# OPAMP_TESTER.net
KiCad netlist of a schematic drawn in Altium Designer
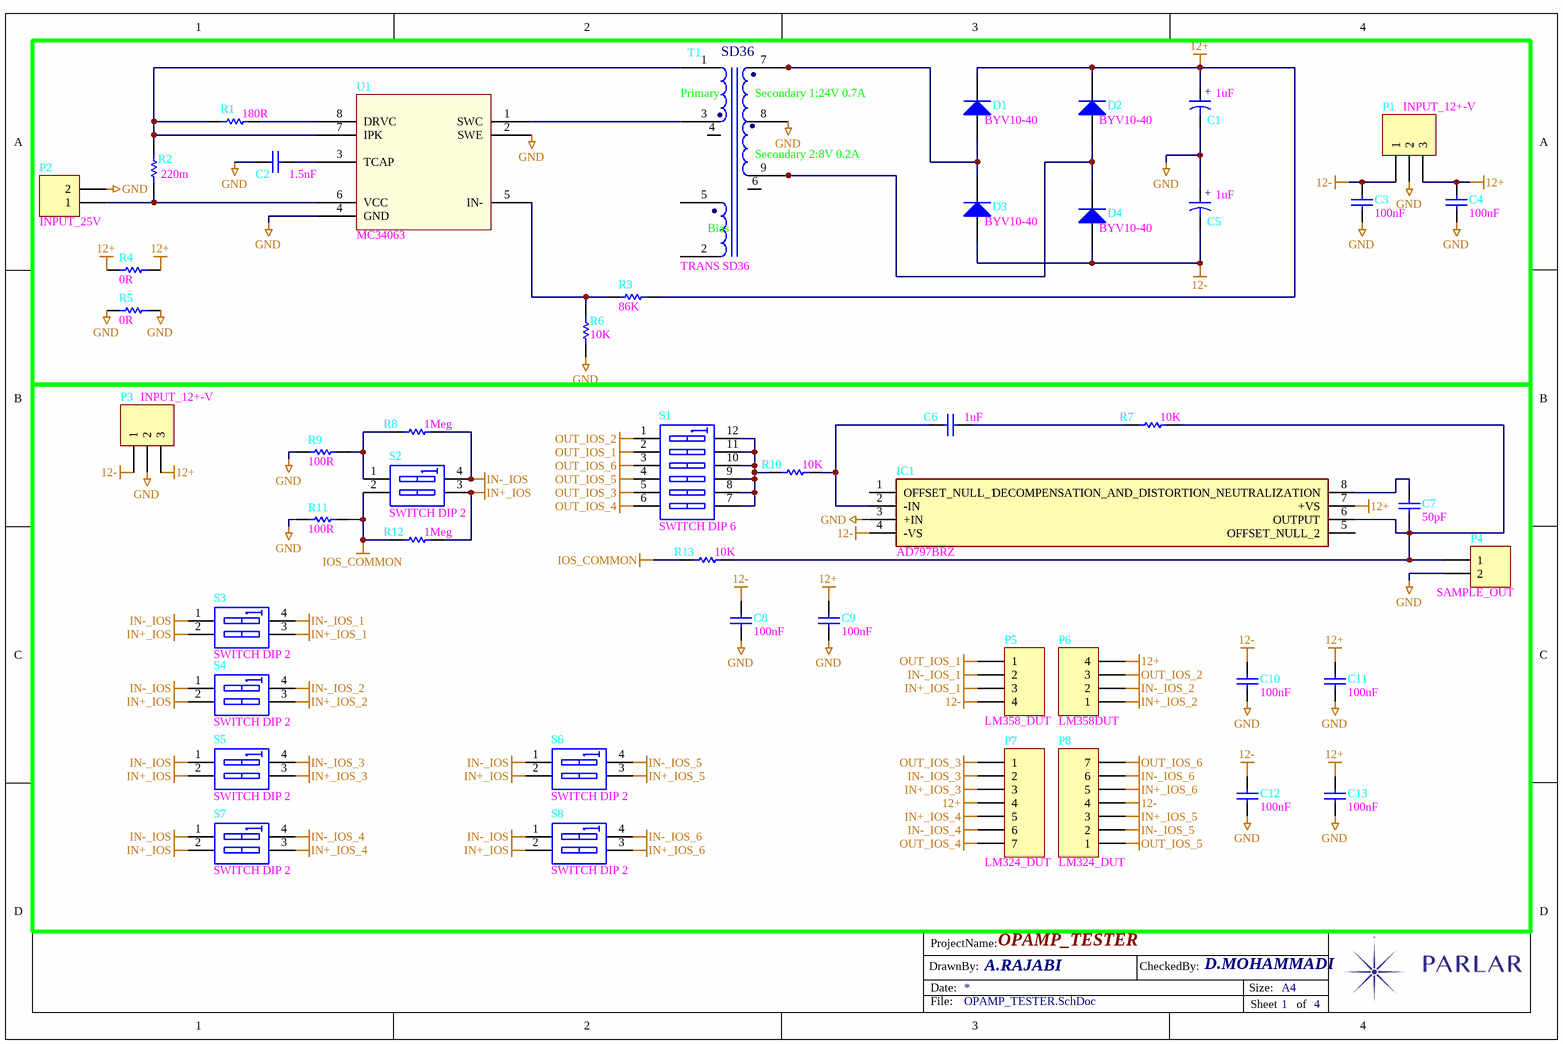
[diagram p0: OPAMP_TESTER.SchDoc]

(export (version "E")
  (design (tool "Eeschema 10.0.6"))
  (components
    (comp (ref "C1")
      (value "1uF")
      (footprint "CAP EL D06.3 P2.5")
      (description "Capacitor  Polarized")
      (fields (field (name "PUBLISHER") "Altium Limited"))
      (libsource (lib "Parlarlib_30") (part "CAP POL"))
    )
    (comp (ref "C2")
      (value "1.5nF")
      (footprint "SMD 0805")
      (description "Capacitor")
      (fields (field (name "PUBLISHER") "Altium Limited"))
      (libsource (lib "Parlarlib_30") (part "CAP"))
    )
    (comp (ref "C3")
      (value "100nF")
      (footprint "SMD 0805")
      (description "Capacitor")
      (fields (field (name "PUBLISHER") "Altium Limited"))
      (libsource (lib "Parlarlib_30") (part "CAP"))
    )
    (comp (ref "C4")
      (value "100nF")
      (footprint "SMD 0805")
      (description "Capacitor")
      (fields (field (name "PUBLISHER") "Altium Limited"))
      (libsource (lib "Parlarlib_30") (part "CAP"))
    )
    (comp (ref "C5")
      (value "1uF")
      (footprint "CAP EL D06.3 P2.5")
      (description "Capacitor  Polarized")
      (fields (field (name "PUBLISHER") "Altium Limited"))
      (libsource (lib "Parlarlib_30") (part "CAP POL"))
    )
    (comp (ref "C6")
      (value "1uF")
      (footprint "SMD 1206")
      (description "Capacitor")
      (fields (field (name "PUBLISHER") "Altium Limited"))
      (libsource (lib "Parlarlib_30") (part "CAP"))
    )
    (comp (ref "C7")
      (value "50pF")
      (footprint "SMD 1206")
      (description "Capacitor")
      (fields (field (name "PUBLISHER") "Altium Limited"))
      (libsource (lib "Parlarlib_30") (part "CAP"))
    )
    (comp (ref "C8")
      (value "100nF")
      (footprint "SMD 0805")
      (description "Capacitor")
      (fields (field (name "PUBLISHER") "Altium Limited"))
      (libsource (lib "Parlarlib_30") (part "CAP"))
    )
    (comp (ref "C9")
      (value "100nF")
      (footprint "SMD 0805")
      (description "Capacitor")
      (fields (field (name "PUBLISHER") "Altium Limited"))
      (libsource (lib "Parlarlib_30") (part "CAP"))
    )
    (comp (ref "C10")
      (value "100nF")
      (footprint "SMD 0805")
      (description "Capacitor")
      (fields (field (name "PUBLISHER") "Altium Limited"))
      (libsource (lib "Parlarlib_30") (part "CAP"))
    )
    (comp (ref "C11")
      (value "100nF")
      (footprint "SMD 0805")
      (description "Capacitor")
      (fields (field (name "PUBLISHER") "Altium Limited"))
      (libsource (lib "Parlarlib_30") (part "CAP"))
    )
    (comp (ref "C12")
      (value "100nF")
      (footprint "SMD 0805")
      (description "Capacitor")
      (fields (field (name "PUBLISHER") "Altium Limited"))
      (libsource (lib "Parlarlib_30") (part "CAP"))
    )
    (comp (ref "C13")
      (value "100nF")
      (footprint "SMD 0805")
      (description "Capacitor")
      (fields (field (name "PUBLISHER") "Altium Limited"))
      (libsource (lib "Parlarlib_30") (part "CAP"))
    )
    (comp (ref "D1")
      (value "BYV10-40")
      (footprint "SMD SMA")
      (description "Typical Diode")
      (libsource (lib "Parlarlib_30") (part "DIODE"))
    )
    (comp (ref "D2")
      (value "BYV10-40")
      (footprint "SMD SMA")
      (description "Typical Diode")
      (libsource (lib "Parlarlib_30") (part "DIODE"))
    )
    (comp (ref "D3")
      (value "BYV10-40")
      (footprint "SMD SMA")
      (description "Typical Diode")
      (libsource (lib "Parlarlib_30") (part "DIODE"))
    )
    (comp (ref "D4")
      (value "BYV10-40")
      (footprint "SMD SMA")
      (description "Typical Diode")
      (libsource (lib "Parlarlib_30") (part "DIODE"))
    )
    (comp (ref "IC1")
      (value "AD797BRZ")
      (footprint "SamacSys:SOIC127P600X175-8N")
      (description "Integrated Circuit")
      (fields (field (name "MOUSER PART NUMBER") "584-AD797BRZ"))
      (libsource (lib "*") (part "AD797BRZ"))
    )
    (comp (ref "P1")
      (value "INPUT_12+-V")
      (footprint "CON XH 3")
      (description "Header, 3-Pin")
      (fields (field (name "PUBLISHER") "Altium Limited"))
      (libsource (lib "Parlarlib_30") (part "CONNECTOR 3"))
    )
    (comp (ref "P2")
      (value "INPUT_25V")
      (footprint "CON XH RA 2")
      (description "Header, 2-Pin")
      (fields (field (name "PUBLISHER") "Altium Limited"))
      (libsource (lib "Parlarlib_30") (part "CONNECTOR 2"))
    )
    (comp (ref "P3")
      (value "INPUT_12+-V")
      (footprint "CON XH 3")
      (description "Header, 3-Pin")
      (fields (field (name "PUBLISHER") "Altium Limited"))
      (libsource (lib "Parlarlib_30") (part "CONNECTOR 3"))
    )
    (comp (ref "P4")
      (value "SAMPLE_OUT")
      (footprint "CON XH 2")
      (description "Header, 2-Pin")
      (fields (field (name "PUBLISHER") "Altium Limited"))
      (libsource (lib "") (part "CONNECTOR 2_1"))
    )
    (comp (ref "P5")
      (value "LM358_DUT")
      (footprint "CON HDR 2.54FM 4")
      (description "Header, 4-Pin")
      (fields (field (name "PUBLISHER") "Altium Limited"))
      (libsource (lib "Parlarlib_30") (part "CONNECTOR 4"))
    )
    (comp (ref "P6")
      (value "LM358DUT")
      (footprint "CON HDR 2.54FM 4")
      (description "Header, 4-Pin")
      (fields (field (name "PUBLISHER") "Altium Limited"))
      (libsource (lib "") (part "CONNECTOR 4_1"))
    )
    (comp (ref "P7")
      (value "LM324_DUT")
      (footprint "CON HDR 2.54FM 7")
      (description "Header, 7-Pin")
      (fields (field (name "PUBLISHER") "Altium Limited"))
      (libsource (lib "") (part "CONNECTOR 7_1"))
    )
    (comp (ref "P8")
      (value "LM324_DUT")
      (footprint "CON HDR 2.54FM 7")
      (description "Header, 7-Pin")
      (fields (field (name "PUBLISHER") "Altium Limited"))
      (libsource (lib "Parlarlib_30") (part "CONNECTOR 7"))
    )
    (comp (ref "R1")
      (value "180R")
      (footprint "SMD 0805")
      (description "Resistor")
      (libsource (lib "Parlarlib_30") (part "RES"))
    )
    (comp (ref "R2")
      (value "220m")
      (footprint "SMD 0805")
      (description "Resistor")
      (libsource (lib "Parlarlib_30") (part "RES"))
    )
    (comp (ref "R3")
      (value "86K")
      (footprint "SMD 1206")
      (description "Resistor")
      (libsource (lib "Parlarlib_30") (part "RES"))
    )
    (comp (ref "R4")
      (value "0R")
      (footprint "SMD 1206")
      (description "Resistor")
      (libsource (lib "Parlarlib_30") (part "RES"))
    )
    (comp (ref "R5")
      (value "0R")
      (footprint "SMD 1206")
      (description "Resistor")
      (libsource (lib "Parlarlib_30") (part "RES"))
    )
    (comp (ref "R6")
      (value "10K")
      (footprint "SMD 0805")
      (description "Resistor")
      (libsource (lib "Parlarlib_30") (part "RES"))
    )
    (comp (ref "R7")
      (value "10K")
      (footprint "SMD 0805")
      (description "Resistor")
      (libsource (lib "Parlarlib_30") (part "RES"))
    )
    (comp (ref "R8")
      (value "1Meg")
      (footprint "SMD 0805")
      (description "Resistor")
      (libsource (lib "Parlarlib_30") (part "RES"))
    )
    (comp (ref "R9")
      (value "100R")
      (footprint "SMD 0805")
      (description "Resistor")
      (libsource (lib "Parlarlib_30") (part "RES"))
    )
    (comp (ref "R10")
      (value "10K")
      (footprint "SMD 1206")
      (description "Resistor")
      (libsource (lib "Parlarlib_30") (part "RES"))
    )
    (comp (ref "R11")
      (value "100R")
      (footprint "SMD 0805")
      (description "Resistor")
      (libsource (lib "Parlarlib_30") (part "RES"))
    )
    (comp (ref "R12")
      (value "1Meg")
      (footprint "SMD 0805")
      (description "Resistor")
      (libsource (lib "Parlarlib_30") (part "RES"))
    )
    (comp (ref "R13")
      (value "10K")
      (footprint "SMD 0805")
      (description "Resistor")
      (libsource (lib "Parlarlib_30") (part "RES"))
    )
    (comp (ref "S1")
      (value "SWITCH DIP 6")
      (footprint "SWITCH DIP 6")
      (description "DIP Switch, 6 Position, SPST")
      (fields (field (name "PUBLISHER") "Altium Limited"))
      (libsource (lib "Parlarlib_30") (part "SWITCH DIP 6"))
    )
    (comp (ref "S2")
      (value "SWITCH DIP 2")
      (footprint "SWITCH DIP 2")
      (description "DIP Switch, 2 Position, SPST")
      (fields (field (name "PUBLISHER") "Altium Limited"))
      (libsource (lib "Parlarlib_30") (part "SWITCH DIP 2"))
    )
    (comp (ref "S3")
      (value "SWITCH DIP 2")
      (footprint "SWITCH DIP 2")
      (description "DIP Switch, 2 Position, SPST")
      (fields (field (name "PUBLISHER") "Altium Limited"))
      (libsource (lib "Parlarlib_30") (part "SWITCH DIP 2"))
    )
    (comp (ref "S4")
      (value "SWITCH DIP 2")
      (footprint "SWITCH DIP 2")
      (description "DIP Switch, 2 Position, SPST")
      (fields (field (name "PUBLISHER") "Altium Limited"))
      (libsource (lib "Parlarlib_30") (part "SWITCH DIP 2"))
    )
    (comp (ref "S5")
      (value "SWITCH DIP 2")
      (footprint "SWITCH DIP 2")
      (description "DIP Switch, 2 Position, SPST")
      (fields (field (name "PUBLISHER") "Altium Limited"))
      (libsource (lib "Parlarlib_30") (part "SWITCH DIP 2"))
    )
    (comp (ref "S6")
      (value "SWITCH DIP 2")
      (footprint "SWITCH DIP 2")
      (description "DIP Switch, 2 Position, SPST")
      (fields (field (name "PUBLISHER") "Altium Limited"))
      (libsource (lib "Parlarlib_30") (part "SWITCH DIP 2"))
    )
    (comp (ref "S7")
      (value "SWITCH DIP 2")
      (footprint "SWITCH DIP 2")
      (description "DIP Switch, 2 Position, SPST")
      (fields (field (name "PUBLISHER") "Altium Limited"))
      (libsource (lib "Parlarlib_30") (part "SWITCH DIP 2"))
    )
    (comp (ref "S8")
      (value "SWITCH DIP 2")
      (footprint "SWITCH DIP 2")
      (description "DIP Switch, 2 Position, SPST")
      (fields (field (name "PUBLISHER") "Altium Limited"))
      (libsource (lib "Parlarlib_30") (part "SWITCH DIP 2"))
    )
    (comp (ref "T1")
      (value "TRANS SD36")
      (footprint "TR EC28/20 VER 5+5")
      (description "Transformer")
      (libsource (lib "Parlarlib_30") (part "TRANS SD36"))
    )
    (comp (ref "U1")
      (value "MC34063")
      (footprint "SMD IC SOP8")
      (libsource (lib "Parlarlib_30") (part "IC MC34063"))
    )
  )
  (nets
    (net (code "1") (name "12+") (class "Default")
      (node (ref "C1") (pin "1") (pinfunction "1_1") (pintype "passive"))
      (node (ref "C11") (pin "2") (pinfunction "2_2") (pintype "passive"))
      (node (ref "C13") (pin "2") (pinfunction "2_2") (pintype "passive"))
      (node (ref "C4") (pin "2") (pinfunction "2_2") (pintype "passive"))
      (node (ref "C9") (pin "2") (pinfunction "2_2") (pintype "passive"))
      (node (ref "D1") (pin "2") (pinfunction "2_2") (pintype "passive"))
      (node (ref "D2") (pin "2") (pinfunction "2_2") (pintype "passive"))
      (node (ref "IC1") (pin "7") (pinfunction "+VS_7") (pintype "passive"))
      (node (ref "P1") (pin "3") (pinfunction "3_3") (pintype "passive"))
      (node (ref "P3") (pin "3") (pinfunction "3_3") (pintype "passive"))
      (node (ref "P6") (pin "4") (pinfunction "4_4") (pintype "passive"))
      (node (ref "P7") (pin "4") (pinfunction "4_4") (pintype "passive"))
      (node (ref "R3") (pin "2") (pinfunction "2_2") (pintype "passive"))
      (node (ref "R4") (pin "1") (pinfunction "1_1") (pintype "passive"))
      (node (ref "R4") (pin "2") (pinfunction "2_2") (pintype "passive"))
    )
    (net (code "2") (name "12-") (class "Default")
      (node (ref "C10") (pin "2") (pinfunction "2_2") (pintype "passive"))
      (node (ref "C12") (pin "2") (pinfunction "2_2") (pintype "passive"))
      (node (ref "C3") (pin "2") (pinfunction "2_2") (pintype "passive"))
      (node (ref "C5") (pin "2") (pinfunction "2_2") (pintype "passive"))
      (node (ref "C8") (pin "2") (pinfunction "2_2") (pintype "passive"))
      (node (ref "D3") (pin "1") (pinfunction "1_1") (pintype "passive"))
      (node (ref "D4") (pin "1") (pinfunction "1_1") (pintype "passive"))
      (node (ref "IC1") (pin "4") (pinfunction "-VS_4") (pintype "passive"))
      (node (ref "P1") (pin "1") (pinfunction "1_1") (pintype "passive"))
      (node (ref "P3") (pin "1") (pinfunction "1_1") (pintype "passive"))
      (node (ref "P5") (pin "4") (pinfunction "4_4") (pintype "passive"))
      (node (ref "P8") (pin "4") (pinfunction "4_4") (pintype "passive"))
    )
    (net (code "3") (name "GND") (class "Default")
      (node (ref "C1") (pin "2") (pinfunction "2_2") (pintype "passive"))
      (node (ref "C10") (pin "1") (pinfunction "1_1") (pintype "passive"))
      (node (ref "C11") (pin "1") (pinfunction "1_1") (pintype "passive"))
      (node (ref "C12") (pin "1") (pinfunction "1_1") (pintype "passive"))
      (node (ref "C13") (pin "1") (pinfunction "1_1") (pintype "passive"))
      (node (ref "C2") (pin "1") (pinfunction "1_1") (pintype "passive"))
      (node (ref "C3") (pin "1") (pinfunction "1_1") (pintype "passive"))
      (node (ref "C4") (pin "1") (pinfunction "1_1") (pintype "passive"))
      (node (ref "C5") (pin "1") (pinfunction "1_1") (pintype "passive"))
      (node (ref "C8") (pin "1") (pinfunction "1_1") (pintype "passive"))
      (node (ref "C9") (pin "1") (pinfunction "1_1") (pintype "passive"))
      (node (ref "IC1") (pin "3") (pinfunction "+IN_3") (pintype "passive"))
      (node (ref "P1") (pin "2") (pinfunction "2_2") (pintype "passive"))
      (node (ref "P2") (pin "2") (pinfunction "2_2") (pintype "passive"))
      (node (ref "P3") (pin "2") (pinfunction "2_2") (pintype "passive"))
      (node (ref "P4") (pin "2") (pinfunction "2_2") (pintype "passive"))
      (node (ref "R11") (pin "1") (pinfunction "1_1") (pintype "passive"))
      (node (ref "R5") (pin "1") (pinfunction "1_1") (pintype "passive"))
      (node (ref "R5") (pin "2") (pinfunction "2_2") (pintype "passive"))
      (node (ref "R6") (pin "2") (pinfunction "2_2") (pintype "passive"))
      (node (ref "R9") (pin "1") (pinfunction "1_1") (pintype "passive"))
      (node (ref "T1") (pin "8") (pinfunction "8_8") (pintype "passive"))
      (node (ref "U1") (pin "2") (pinfunction "SWE_2") (pintype "passive"))
      (node (ref "U1") (pin "4") (pinfunction "GND_4") (pintype "power_in"))
    )
    (net (code "4") (name "IN+_IOS") (class "Default")
      (node (ref "R12") (pin "2") (pinfunction "2_2") (pintype "passive"))
      (node (ref "S2") (pin "3") (pinfunction "B2_3") (pintype "passive"))
      (node (ref "S3") (pin "2") (pinfunction "A2_2") (pintype "passive"))
      (node (ref "S4") (pin "2") (pinfunction "A2_2") (pintype "passive"))
      (node (ref "S5") (pin "2") (pinfunction "A2_2") (pintype "passive"))
      (node (ref "S6") (pin "2") (pinfunction "A2_2") (pintype "passive"))
      (node (ref "S7") (pin "2") (pinfunction "A2_2") (pintype "passive"))
      (node (ref "S8") (pin "2") (pinfunction "A2_2") (pintype "passive"))
    )
    (net (code "5") (name "IN+_IOS_1") (class "Default")
      (node (ref "P5") (pin "3") (pinfunction "3_3") (pintype "passive"))
      (node (ref "S3") (pin "3") (pinfunction "B2_3") (pintype "passive"))
    )
    (net (code "6") (name "IN+_IOS_2") (class "Default")
      (node (ref "P6") (pin "1") (pinfunction "1_1") (pintype "passive"))
      (node (ref "S4") (pin "3") (pinfunction "B2_3") (pintype "passive"))
    )
    (net (code "7") (name "IN+_IOS_3") (class "Default")
      (node (ref "P7") (pin "3") (pinfunction "3_3") (pintype "passive"))
      (node (ref "S5") (pin "3") (pinfunction "B2_3") (pintype "passive"))
    )
    (net (code "8") (name "IN+_IOS_4") (class "Default")
      (node (ref "P7") (pin "5") (pinfunction "5_5") (pintype "passive"))
      (node (ref "S7") (pin "3") (pinfunction "B2_3") (pintype "passive"))
    )
    (net (code "9") (name "IN+_IOS_5") (class "Default")
      (node (ref "P8") (pin "3") (pinfunction "3_3") (pintype "passive"))
      (node (ref "S6") (pin "3") (pinfunction "B2_3") (pintype "passive"))
    )
    (net (code "10") (name "IN+_IOS_6") (class "Default")
      (node (ref "P8") (pin "5") (pinfunction "5_5") (pintype "passive"))
      (node (ref "S8") (pin "3") (pinfunction "B2_3") (pintype "passive"))
    )
    (net (code "11") (name "IN-_IOS") (class "Default")
      (node (ref "R8") (pin "2") (pinfunction "2_2") (pintype "passive"))
      (node (ref "S2") (pin "4") (pinfunction "B1_4") (pintype "passive"))
      (node (ref "S3") (pin "1") (pinfunction "A1_1") (pintype "passive"))
      (node (ref "S4") (pin "1") (pinfunction "A1_1") (pintype "passive"))
      (node (ref "S5") (pin "1") (pinfunction "A1_1") (pintype "passive"))
      (node (ref "S6") (pin "1") (pinfunction "A1_1") (pintype "passive"))
      (node (ref "S7") (pin "1") (pinfunction "A1_1") (pintype "passive"))
      (node (ref "S8") (pin "1") (pinfunction "A1_1") (pintype "passive"))
    )
    (net (code "12") (name "IN-_IOS_1") (class "Default")
      (node (ref "P5") (pin "2") (pinfunction "2_2") (pintype "passive"))
      (node (ref "S3") (pin "4") (pinfunction "B1_4") (pintype "passive"))
    )
    (net (code "13") (name "IN-_IOS_2") (class "Default")
      (node (ref "P6") (pin "2") (pinfunction "2_2") (pintype "passive"))
      (node (ref "S4") (pin "4") (pinfunction "B1_4") (pintype "passive"))
    )
    (net (code "14") (name "IN-_IOS_3") (class "Default")
      (node (ref "P7") (pin "2") (pinfunction "2_2") (pintype "passive"))
      (node (ref "S5") (pin "4") (pinfunction "B1_4") (pintype "passive"))
    )
    (net (code "15") (name "IN-_IOS_4") (class "Default")
      (node (ref "P7") (pin "6") (pinfunction "6_6") (pintype "passive"))
      (node (ref "S7") (pin "4") (pinfunction "B1_4") (pintype "passive"))
    )
    (net (code "16") (name "IN-_IOS_5") (class "Default")
      (node (ref "P8") (pin "2") (pinfunction "2_2") (pintype "passive"))
      (node (ref "S6") (pin "4") (pinfunction "B1_4") (pintype "passive"))
    )
    (net (code "17") (name "IN-_IOS_6") (class "Default")
      (node (ref "P8") (pin "6") (pinfunction "6_6") (pintype "passive"))
      (node (ref "S8") (pin "4") (pinfunction "B1_4") (pintype "passive"))
    )
    (net (code "18") (name "IOS_COMMON") (class "Default")
      (node (ref "R11") (pin "2") (pinfunction "2_2") (pintype "passive"))
      (node (ref "R12") (pin "1") (pinfunction "1_1") (pintype "passive"))
      (node (ref "R13") (pin "1") (pinfunction "1_1") (pintype "passive"))
      (node (ref "S2") (pin "2") (pinfunction "A2_2") (pintype "passive"))
    )
    (net (code "19") (name "Net-(C6-Pad1)") (class "Default")
      (node (ref "C6") (pin "1") (pinfunction "1_1") (pintype "passive"))
      (node (ref "R7") (pin "1") (pinfunction "1_1") (pintype "passive"))
    )
    (net (code "20") (name "Net-(D1-Pad1)") (class "Default")
      (node (ref "D1") (pin "1") (pinfunction "1_1") (pintype "passive"))
      (node (ref "D3") (pin "2") (pinfunction "2_2") (pintype "passive"))
      (node (ref "T1") (pin "6") (pinfunction "6_6") (pintype "passive"))
      (node (ref "T1") (pin "7") (pinfunction "7_7") (pintype "passive"))
    )
    (net (code "21") (name "Net-(D2-Pad1)") (class "Default")
      (node (ref "D2") (pin "1") (pinfunction "1_1") (pintype "passive"))
      (node (ref "D4") (pin "2") (pinfunction "2_2") (pintype "passive"))
      (node (ref "T1") (pin "10") (pinfunction "10_10") (pintype "passive"))
      (node (ref "T1") (pin "9") (pinfunction "9_9") (pintype "passive"))
    )
    (net (code "22") (name "Net-(IC1--IN)") (class "Default")
      (node (ref "C6") (pin "2") (pinfunction "2_2") (pintype "passive"))
      (node (ref "IC1") (pin "2") (pinfunction "-IN_2") (pintype "passive"))
      (node (ref "R10") (pin "2") (pinfunction "2_2") (pintype "passive"))
    )
    (net (code "23") (name "Net-(IC1-DECOMPENSATION_AND_DISTORTION_NEUTRALIZATION)") (class "Default")
      (node (ref "C7") (pin "1") (pinfunction "1_1") (pintype "passive"))
      (node (ref "IC1") (pin "8") (pinfunction "DECOMPENSATION_AND_DISTORTION_NEUTRALIZATION_8") (pintype "passive"))
    )
    (net (code "24") (name "Net-(IC1-OUTPUT)") (class "Default")
      (node (ref "C7") (pin "2") (pinfunction "2_2") (pintype "passive"))
      (node (ref "IC1") (pin "6") (pinfunction "OUTPUT_6") (pintype "passive"))
      (node (ref "P4") (pin "1") (pinfunction "1_1") (pintype "passive"))
      (node (ref "R13") (pin "2") (pinfunction "2_2") (pintype "passive"))
      (node (ref "R7") (pin "2") (pinfunction "2_2") (pintype "passive"))
    )
    (net (code "25") (name "Net-(S1-B1)") (class "Default")
      (node (ref "R10") (pin "1") (pinfunction "1_1") (pintype "passive"))
      (node (ref "S1") (pin "10") (pinfunction "B3_10") (pintype "passive"))
      (node (ref "S1") (pin "11") (pinfunction "B2_11") (pintype "passive"))
      (node (ref "S1") (pin "12") (pinfunction "B1_12") (pintype "passive"))
      (node (ref "S1") (pin "7") (pinfunction "B6_7") (pintype "passive"))
      (node (ref "S1") (pin "8") (pinfunction "B5_8") (pintype "passive"))
      (node (ref "S1") (pin "9") (pinfunction "B4_9") (pintype "passive"))
    )
    (net (code "26") (name "Net-(S2-A1)") (class "Default")
      (node (ref "R8") (pin "1") (pinfunction "1_1") (pintype "passive"))
      (node (ref "R9") (pin "2") (pinfunction "2_2") (pintype "passive"))
      (node (ref "S2") (pin "1") (pinfunction "A1_1") (pintype "passive"))
    )
    (net (code "27") (name "Net-(U1-DRVC)") (class "Default")
      (node (ref "R1") (pin "2") (pinfunction "2_2") (pintype "passive"))
      (node (ref "U1") (pin "8") (pinfunction "DRVC_8") (pintype "open_collector"))
    )
    (net (code "28") (name "Net-(U1-IN-)") (class "Default")
      (node (ref "R3") (pin "1") (pinfunction "1_1") (pintype "passive"))
      (node (ref "R6") (pin "1") (pinfunction "1_1") (pintype "passive"))
      (node (ref "U1") (pin "5") (pinfunction "IN-_5") (pintype "passive"))
    )
    (net (code "29") (name "Net-(U1-IPK)") (class "Default")
      (node (ref "R1") (pin "1") (pinfunction "1_1") (pintype "passive"))
      (node (ref "R2") (pin "1") (pinfunction "1_1") (pintype "passive"))
      (node (ref "T1") (pin "1") (pinfunction "1_1") (pintype "passive"))
      (node (ref "U1") (pin "7") (pinfunction "IPK_7") (pintype "passive"))
    )
    (net (code "30") (name "Net-(U1-SWC)") (class "Default")
      (node (ref "T1") (pin "3") (pinfunction "3_3") (pintype "passive"))
      (node (ref "U1") (pin "1") (pinfunction "SWC_1") (pintype "passive"))
    )
    (net (code "31") (name "Net-(U1-TCAP)") (class "Default")
      (node (ref "C2") (pin "2") (pinfunction "2_2") (pintype "passive"))
      (node (ref "U1") (pin "3") (pinfunction "TCAP_3") (pintype "passive"))
    )
    (net (code "32") (name "Net-(U1-VCC)") (class "Default")
      (node (ref "P2") (pin "1") (pinfunction "1_1") (pintype "passive"))
      (node (ref "R2") (pin "2") (pinfunction "2_2") (pintype "passive"))
      (node (ref "U1") (pin "6") (pinfunction "VCC_6") (pintype "power_in"))
    )
    (net (code "33") (name "OUT_IOS_1") (class "Default")
      (node (ref "P5") (pin "1") (pinfunction "1_1") (pintype "passive"))
      (node (ref "S1") (pin "2") (pinfunction "A2_2") (pintype "passive"))
    )
    (net (code "34") (name "OUT_IOS_2") (class "Default")
      (node (ref "P6") (pin "3") (pinfunction "3_3") (pintype "passive"))
      (node (ref "S1") (pin "1") (pinfunction "A1_1") (pintype "passive"))
    )
    (net (code "35") (name "OUT_IOS_3") (class "Default")
      (node (ref "P7") (pin "1") (pinfunction "1_1") (pintype "passive"))
      (node (ref "S1") (pin "5") (pinfunction "A5_5") (pintype "passive"))
    )
    (net (code "36") (name "OUT_IOS_4") (class "Default")
      (node (ref "P7") (pin "7") (pinfunction "7_7") (pintype "passive"))
      (node (ref "S1") (pin "6") (pinfunction "A6_6") (pintype "passive"))
    )
    (net (code "37") (name "OUT_IOS_5") (class "Default")
      (node (ref "P8") (pin "1") (pinfunction "1_1") (pintype "passive"))
      (node (ref "S1") (pin "4") (pinfunction "A4_4") (pintype "passive"))
    )
    (net (code "38") (name "OUT_IOS_6") (class "Default")
      (node (ref "P8") (pin "7") (pinfunction "7_7") (pintype "passive"))
      (node (ref "S1") (pin "3") (pinfunction "A3_3") (pintype "passive"))
    )
    (net (code "39") (name "unconnected-(IC1-OFFSET_NULL_1-Pad1)") (class "Default")
      (node (ref "IC1") (pin "1") (pinfunction "OFFSET_NULL_1_1") (pintype "passive"))
    )
    (net (code "40") (name "unconnected-(IC1-OFFSET_NULL_2-Pad5)") (class "Default")
      (node (ref "IC1") (pin "5") (pinfunction "OFFSET_NULL_2_5") (pintype "passive"))
    )
    (net (code "41") (name "unconnected-(T1-Pad2)") (class "Default")
      (node (ref "T1") (pin "2") (pinfunction "2_2") (pintype "passive"))
    )
    (net (code "42") (name "unconnected-(T1-Pad4)") (class "Default")
      (node (ref "T1") (pin "4") (pinfunction "4_4") (pintype "passive"))
    )
    (net (code "43") (name "unconnected-(T1-Pad5)") (class "Default")
      (node (ref "T1") (pin "5") (pinfunction "5_5") (pintype "passive"))
    )
    (net (code "44") (name "unconnected-(T1-Pad6)") (class "Default")
      (node (ref "T1") (pin "6") (pinfunction "6_6") (pintype "passive"))
    )
  )
)
